# analog_channel.net
KiCad netlist of a schematic drawn in Altium Designer
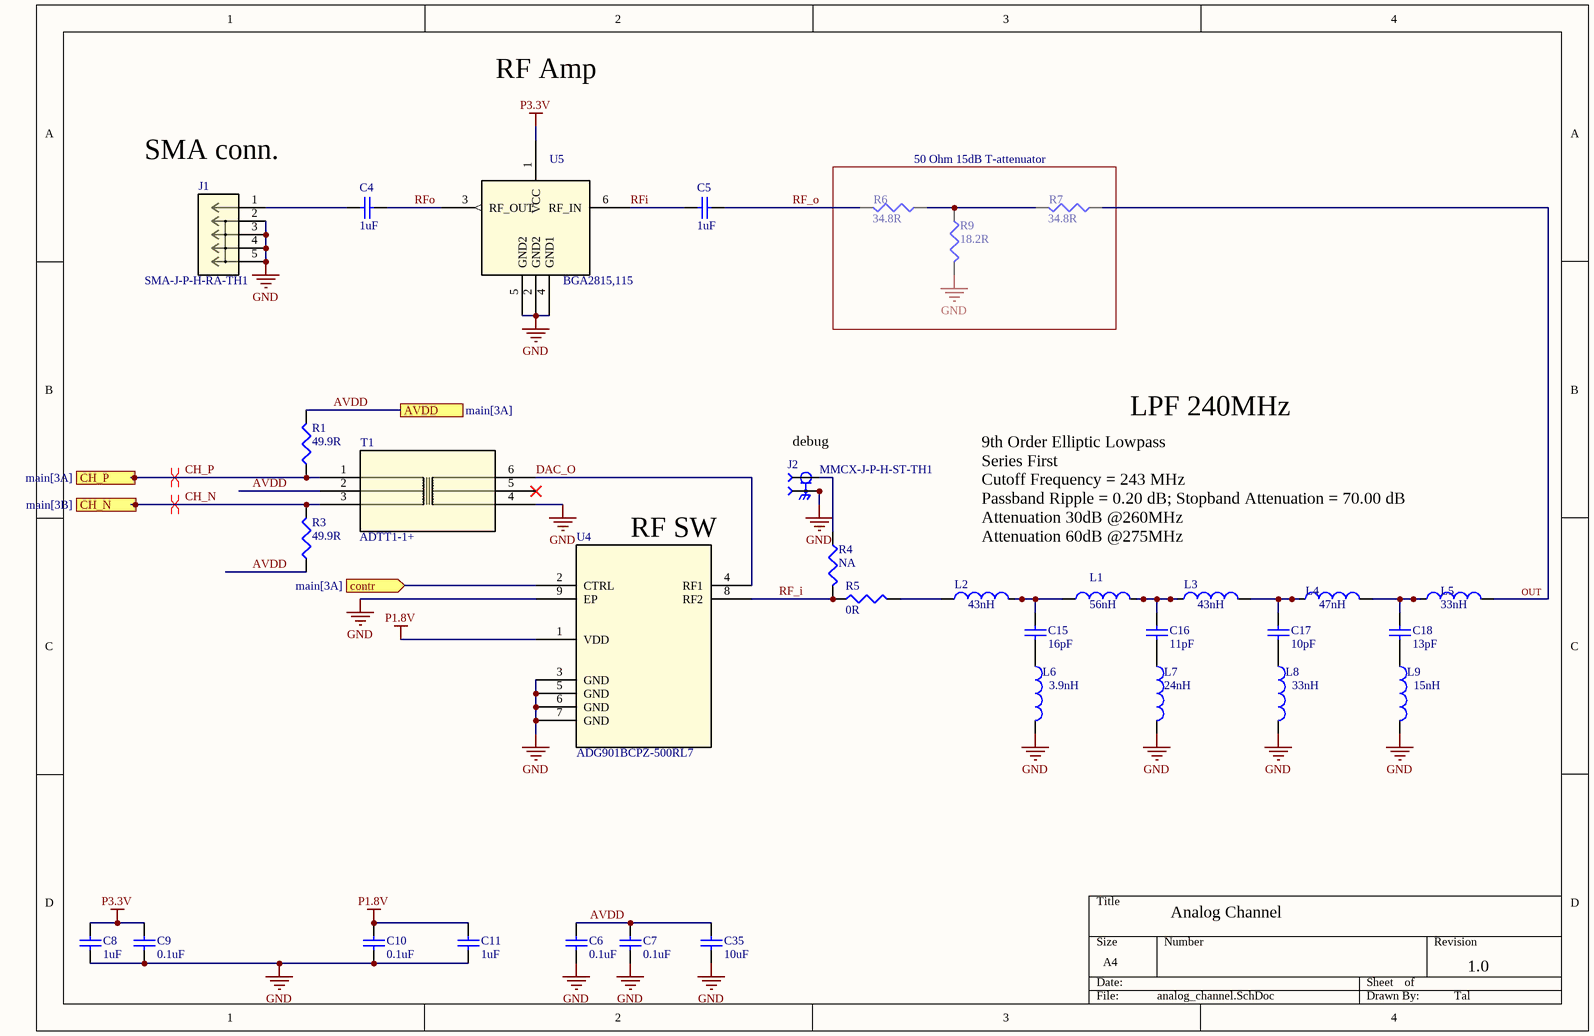
[diagram p0: analog_channel.SchDoc]

(export (version "E")
  (design (tool "Eeschema 10.0.6"))
  (components
    (comp (ref "C4")
      (value "1uF 25V")
      (footprint "Landa_PCB:C0402")
      (description "CAP CER 1uF 25V X5R 0402")
      (fields
        (field (name "MANUFACTURER PART NUMBER") "C1005C0G1H6R8D")
        (field (name "MANUFACTURER") "TDK Corporation")
        (field (name "CAPACITANCE") "1uF")
      )
      (libsource (lib "L_SCH_C") (part "CAP CER 6.8pF 50V NP0 0402"))
    )
    (comp (ref "C5")
      (value "1uF 25V")
      (footprint "Landa_PCB:C0402")
      (description "CAP CER 1uF 25V X5R 0402")
      (fields
        (field (name "MANUFACTURER PART NUMBER") "C1005C0G1H6R8D")
        (field (name "MANUFACTURER") "TDK Corporation")
        (field (name "CAPACITANCE") "1uF")
      )
      (libsource (lib "L_SCH_C") (part "CAP CER 6.8pF 50V NP0 0402"))
    )
    (comp (ref "C6")
      (value "0.1uF 50V")
      (footprint "Landa_PCB:C0402")
      (description "CAP CER 0.1uF 50V NP0 0402")
      (fields
        (field (name "MANUFACTURER PART NUMBER") "C1005C0G1H6R8D")
        (field (name "MANUFACTURER") "TDK Corporation")
        (field (name "CAPACITANCE") "0.1uF")
      )
      (libsource (lib "L_SCH_C") (part "CAP CER 6.8pF 50V NP0 0402"))
    )
    (comp (ref "C7")
      (value "0.1uF 50V")
      (footprint "Landa_PCB:C0402")
      (description "CAP CER 0.1uF 50V NP0 0402")
      (fields
        (field (name "MANUFACTURER PART NUMBER") "C1005C0G1H6R8D")
        (field (name "MANUFACTURER") "TDK Corporation")
        (field (name "CAPACITANCE") "0.1uF")
      )
      (libsource (lib "L_SCH_C") (part "CAP CER 6.8pF 50V NP0 0402"))
    )
    (comp (ref "C8")
      (value "1uF 25V")
      (footprint "Landa_PCB:C0402")
      (description "CAP CER 1uF 25V X5R 0402")
      (fields
        (field (name "MANUFACTURER PART NUMBER") "C1005C0G1H6R8D")
        (field (name "MANUFACTURER") "TDK Corporation")
        (field (name "CAPACITANCE") "1uF")
      )
      (libsource (lib "L_SCH_C") (part "CAP CER 6.8pF 50V NP0 0402"))
    )
    (comp (ref "C9")
      (value "0.1uF 50V")
      (footprint "Landa_PCB:C0402")
      (description "CAP CER 0.1uF 50V NP0 0402")
      (fields
        (field (name "MANUFACTURER PART NUMBER") "C1005C0G1H6R8D")
        (field (name "MANUFACTURER") "TDK Corporation")
        (field (name "CAPACITANCE") "0.1uF")
      )
      (libsource (lib "L_SCH_C") (part "CAP CER 6.8pF 50V NP0 0402"))
    )
    (comp (ref "C10")
      (value "0.1uF 50V")
      (footprint "Landa_PCB:C0402")
      (description "CAP CER 0.1uF 50V NP0 0402")
      (fields
        (field (name "MANUFACTURER PART NUMBER") "C1005C0G1H6R8D")
        (field (name "MANUFACTURER") "TDK Corporation")
        (field (name "CAPACITANCE") "0.1uF")
      )
      (libsource (lib "L_SCH_C") (part "CAP CER 6.8pF 50V NP0 0402"))
    )
    (comp (ref "C11")
      (value "1uF 25V")
      (footprint "Landa_PCB:C0402")
      (description "CAP CER 1uF 25V X5R 0402")
      (fields
        (field (name "MANUFACTURER PART NUMBER") "C1005C0G1H6R8D")
        (field (name "MANUFACTURER") "TDK Corporation")
        (field (name "CAPACITANCE") "1uF")
      )
      (libsource (lib "L_SCH_C") (part "CAP CER 6.8pF 50V NP0 0402"))
    )
    (comp (ref "C15")
      (value "16pF 50V")
      (footprint "Landa_PCB:C0402")
      (description "CAP CER 16PF 50V 5% NP0 0402")
      (fields
        (field (name "MANUFACTURER") "TDK Corporation")
        (field (name "MANUFACTURER PART NUMBER") "C1005C0G1H200J")
        (field (name "CAPACITANCE") "16pF")
      )
      (libsource (lib "L_SCH_C") (part "CAP CER 20pF 50V 5% NP0 0402"))
    )
    (comp (ref "C16")
      (value "11pF 50V")
      (footprint "Landa_PCB:C0402")
      (description "CAP CER 11PF 50V 5% NP0 0402")
      (fields
        (field (name "MANUFACTURER") "TDK Corporation")
        (field (name "MANUFACTURER PART NUMBER") "C1005C0G1H200J")
        (field (name "CAPACITANCE") "11pF")
      )
      (libsource (lib "L_SCH_C") (part "CAP CER 20pF 50V 5% NP0 0402"))
    )
    (comp (ref "C17")
      (value "10pF 50V")
      (footprint "Landa_PCB:C0402")
      (description "CAP CER 10PF 50V 5% NP0 0402")
      (fields
        (field (name "MANUFACTURER") "TDK Corporation")
        (field (name "MANUFACTURER PART NUMBER") "C1005C0G1H200J")
        (field (name "CAPACITANCE") "10pF")
      )
      (libsource (lib "L_SCH_C") (part "CAP CER 20pF 50V 5% NP0 0402"))
    )
    (comp (ref "C18")
      (value "13pF 50V")
      (footprint "Landa_PCB:C0402")
      (description "CAP CER 13PF 50V 5% NP0 0402")
      (fields
        (field (name "MANUFACTURER") "TDK Corporation")
        (field (name "MANUFACTURER PART NUMBER") "C1005C0G1H200J")
        (field (name "CAPACITANCE") "13pF")
      )
      (libsource (lib "L_SCH_C") (part "CAP CER 20pF 50V 5% NP0 0402"))
    )
    (comp (ref "C35")
      (value "10uF 10V")
      (footprint "Landa_PCB:C0402")
      (description "CAP CER 10uF 10V X5R 0402")
      (fields
        (field (name "MANUFACTURER PART NUMBER") "C1005C0G1H6R8D")
        (field (name "MANUFACTURER") "TDK Corporation")
        (field (name "CAPACITANCE") "10uF")
      )
      (libsource (lib "L_SCH_C") (part "CAP CER 6.8pF 50V NP0 0402"))
    )
    (comp (ref "J1")
      (value "SMA-J-P-H-RA-TH1")
      (footprint "CONN_SMA-J-P-H-RA-TH1_SAI")
      (description "No Description Available")
      (fields (field (name "COPYRIGHT") "Copyright (C) 2023 Ultra Librarian. All rights reserved."))
      (libsource (lib "SMA-J-P-H-RA-TH1") (part "SMA-J-P-H-RA-TH1"))
    )
    (comp (ref "J2")
      (value "MMCX-J-P-H-ST-TH1")
      (footprint "SAMTEC_MMCX-J-P-H-ST-TH1")
      (description "MMCX STRAIGHT, THROUGH HOLE JACK- 50 OHM")
      (fields (field (name "MF") "Samtec"))
      (libsource (lib "MMCX-J-P-H-ST-TH1") (part "MMCX-J-P-H-ST-TH1"))
    )
    (comp (ref "L1")
      (value "56nH")
      (footprint "0402-A")
      (description "Inductor")
      (fields (field (name "PUBLISHER") "Altium Limited"))
      (libsource (lib "Miscellaneous Devices") (part "Inductor"))
    )
    (comp (ref "L2")
      (value "43nH")
      (footprint "0402-A")
      (description "Inductor")
      (fields (field (name "PUBLISHER") "Altium Limited"))
      (libsource (lib "Miscellaneous Devices") (part "Inductor"))
    )
    (comp (ref "L3")
      (value "43nH")
      (footprint "0402-A")
      (description "Inductor")
      (fields (field (name "PUBLISHER") "Altium Limited"))
      (libsource (lib "Miscellaneous Devices") (part "Inductor"))
    )
    (comp (ref "L4")
      (value "47nH")
      (footprint "0402-A")
      (description "Inductor")
      (fields (field (name "PUBLISHER") "Altium Limited"))
      (libsource (lib "Miscellaneous Devices") (part "Inductor"))
    )
    (comp (ref "L5")
      (value "33nH")
      (footprint "0402-A")
      (description "Inductor")
      (fields (field (name "PUBLISHER") "Altium Limited"))
      (libsource (lib "Miscellaneous Devices") (part "Inductor"))
    )
    (comp (ref "L6")
      (value "3.9nH")
      (footprint "0402-A")
      (description "Inductor")
      (fields (field (name "PUBLISHER") "Altium Limited"))
      (libsource (lib "Miscellaneous Devices") (part "Inductor"))
    )
    (comp (ref "L7")
      (value "24nH")
      (footprint "0402-A")
      (description "Inductor")
      (fields (field (name "PUBLISHER") "Altium Limited"))
      (libsource (lib "Miscellaneous Devices") (part "Inductor"))
    )
    (comp (ref "L8")
      (value "33nH")
      (footprint "0402-A")
      (description "Inductor")
      (fields (field (name "PUBLISHER") "Altium Limited"))
      (libsource (lib "Miscellaneous Devices") (part "Inductor"))
    )
    (comp (ref "L9")
      (value "15nH")
      (footprint "0402-A")
      (description "Inductor")
      (fields (field (name "PUBLISHER") "Altium Limited"))
      (libsource (lib "Miscellaneous Devices") (part "Inductor"))
    )
    (comp (ref "R1")
      (value "49.9R")
      (footprint "Landa_PCB:R0402")
      (description "RES 49.9 OHM 1/10W 1% 0402 SMD")
      (fields
        (field (name "MANUFACTURER PART NUMBER") "ERJ-2RKF1000X")
        (field (name "MANUFACTURER") "Panasonic Electronic Components")
      )
      (libsource (lib "L_SCH_R") (part "RES 100 OHM 1/10W 1% 0402 SMD"))
    )
    (comp (ref "R3")
      (value "49.9R")
      (footprint "Landa_PCB:R0402")
      (description "RES 49.9 OHM 1/10W 1% 0402 SMD")
      (fields
        (field (name "MANUFACTURER PART NUMBER") "ERJ-2RKF1000X")
        (field (name "MANUFACTURER") "Panasonic Electronic Components")
      )
      (libsource (lib "L_SCH_R") (part "RES 100 OHM 1/10W 1% 0402 SMD"))
    )
    (comp (ref "R4")
      (value "NA")
      (footprint "r0402")
      (description "RES 0 OHM 1/10W 1% 0402 SMD")
      (fields
        (field (name "MANUFACTURER PART NUMBER") "ERJ-2RKF1000X")
        (field (name "MANUFACTURER") "Panasonic Electronic Components")
      )
      (libsource (lib "L_SCH_R") (part "RES 100 OHM 1/10W 1% 0402 SMD"))
    )
    (comp (ref "R5")
      (value "0R")
      (footprint "r0402")
      (description "RES 0 OHM 1/10W 1% 0402 SMD")
      (fields
        (field (name "MANUFACTURER PART NUMBER") "ERJ-2RKF1000X")
        (field (name "MANUFACTURER") "Panasonic Electronic Components")
      )
      (libsource (lib "L_SCH_R") (part "RES 100 OHM 1/10W 1% 0402 SMD"))
    )
    (comp (ref "R6")
      (value "34.8R")
      (footprint "r0402")
      (description "RES 34.8 OHM 1/10W 1% 0402 SMD")
      (fields
        (field (name "MANUFACTURER PART NUMBER") "ERJ-2RKF1000X")
        (field (name "MANUFACTURER") "Panasonic Electronic Components")
      )
      (libsource (lib "L_SCH_R") (part "RES 100 OHM 1/10W 1% 0402 SMD"))
    )
    (comp (ref "R7")
      (value "34.8R")
      (footprint "r0402")
      (description "RES 34.8 OHM 1/10W 1% 0402 SMD")
      (fields
        (field (name "MANUFACTURER PART NUMBER") "ERJ-2RKF1000X")
        (field (name "MANUFACTURER") "Panasonic Electronic Components")
      )
      (libsource (lib "L_SCH_R") (part "RES 100 OHM 1/10W 1% 0402 SMD"))
    )
    (comp (ref "R9")
      (value "18.2R")
      (footprint "r0402")
      (description "RES 18.2 OHM 1/10W 1% 0402 SMD")
      (fields
        (field (name "MANUFACTURER PART NUMBER") "ERJ-2RKF1000X")
        (field (name "MANUFACTURER") "Panasonic Electronic Components")
      )
      (libsource (lib "L_SCH_R") (part "RES 100 OHM 1/10W 1% 0402 SMD"))
    )
    (comp (ref "T1")
      (value "ADTT1-1+")
      (footprint "CD542_MNC")
      (description "No Description Available")
      (fields (field (name "COPYRIGHT") "Copyright (C) 2023 Ultra Librarian. All rights reserved."))
      (libsource (lib "ADTT1-1&plus_") (part "ADTT1-1+"))
    )
    (comp (ref "U4")
      (value "ADG901BCPZ-500RL7")
      (footprint "CP_8_2_ADI")
      (description "No Description Available")
      (fields (field (name "COPYRIGHT") "Copyright (C) 2023 Ultra Librarian. All rights reserved."))
      (libsource (lib "ADG901BCPZ-500RL7") (part "ADG901BCPZ-500RL7"))
    )
    (comp (ref "U5")
      (value "BGA2815,115")
      (footprint "SOT_2815,115_NXP")
      (description "No Description Available")
      (fields (field (name "COPYRIGHT") "Copyright (C) 2023 Ultra Librarian. All rights reserved."))
      (libsource (lib "BGA2815,115") (part "BGA2815,115"))
    )
  )
  (nets
    (net (code "1") (name "/AVDD") (class "Default")
      (node (ref "C35") (pin "2") (pinfunction "2_2") (pintype "passive"))
      (node (ref "C6") (pin "2") (pinfunction "2_2") (pintype "passive"))
      (node (ref "C7") (pin "2") (pinfunction "2_2") (pintype "passive"))
      (node (ref "R1") (pin "2") (pinfunction "2_2") (pintype "passive"))
      (node (ref "R3") (pin "1") (pinfunction "1_1") (pintype "passive"))
      (node (ref "T1") (pin "2") (pinfunction "2_2") (pintype "passive"))
    )
    (net (code "2") (name "/CH_N") (class "Default")
      (node (ref "R3") (pin "2") (pinfunction "2_2") (pintype "passive"))
      (node (ref "T1") (pin "3") (pinfunction "3_3") (pintype "passive"))
    )
    (net (code "3") (name "/CH_P") (class "Default")
      (node (ref "R1") (pin "1") (pinfunction "1_1") (pintype "passive"))
      (node (ref "T1") (pin "1") (pinfunction "1_1") (pintype "passive"))
    )
    (net (code "4") (name "/DAC_O") (class "Default")
      (node (ref "T1") (pin "6") (pinfunction "6_6") (pintype "passive"))
      (node (ref "U4") (pin "4") (pinfunction "RF1_4") (pintype "passive"))
    )
    (net (code "5") (name "/OUT") (class "Default")
      (node (ref "L5") (pin "2") (pinfunction "2_2") (pintype "passive"))
      (node (ref "R7") (pin "1") (pinfunction "1_1") (pintype "passive"))
    )
    (net (code "6") (name "/RF_i") (class "Default")
      (node (ref "R4") (pin "2") (pinfunction "2_2") (pintype "passive"))
      (node (ref "R5") (pin "1") (pinfunction "1_1") (pintype "passive"))
      (node (ref "U4") (pin "8") (pinfunction "RF2_8") (pintype "passive"))
    )
    (net (code "7") (name "/RF_o") (class "Default")
      (node (ref "C5") (pin "2") (pinfunction "2_2") (pintype "passive"))
      (node (ref "R6") (pin "2") (pinfunction "2_2") (pintype "passive"))
    )
    (net (code "8") (name "/RFi") (class "Default")
      (node (ref "C5") (pin "1") (pinfunction "1_1") (pintype "passive"))
      (node (ref "U5") (pin "6") (pinfunction "RF_IN_6") (pintype "passive"))
    )
    (net (code "9") (name "/RFo") (class "Default")
      (node (ref "C4") (pin "2") (pinfunction "2_2") (pintype "passive"))
      (node (ref "U5") (pin "3") (pinfunction "RF_OUT_3") (pintype "output"))
    )
    (net (code "10") (name "/contr") (class "Default")
      (node (ref "U4") (pin "2") (pinfunction "CTRL_2") (pintype "passive"))
    )
    (net (code "11") (name "GND") (class "Default")
      (node (ref "C10") (pin "1") (pinfunction "1_1") (pintype "passive"))
      (node (ref "C11") (pin "1") (pinfunction "1_1") (pintype "passive"))
      (node (ref "C35") (pin "1") (pinfunction "1_1") (pintype "passive"))
      (node (ref "C6") (pin "1") (pinfunction "1_1") (pintype "passive"))
      (node (ref "C7") (pin "1") (pinfunction "1_1") (pintype "passive"))
      (node (ref "C8") (pin "1") (pinfunction "1_1") (pintype "passive"))
      (node (ref "C9") (pin "1") (pinfunction "1_1") (pintype "passive"))
      (node (ref "J1") (pin "2") (pinfunction "2_2") (pintype "passive"))
      (node (ref "J1") (pin "3") (pinfunction "3_3") (pintype "passive"))
      (node (ref "J1") (pin "4") (pinfunction "4_4") (pintype "passive"))
      (node (ref "J1") (pin "5") (pinfunction "5_5") (pintype "passive"))
      (node (ref "J2") (pin "S1") (pinfunction "2_S1") (pintype "passive"))
      (node (ref "J2") (pin "S2") (pinfunction "2_S2") (pintype "passive"))
      (node (ref "J2") (pin "S3") (pinfunction "2_S3") (pintype "passive"))
      (node (ref "J2") (pin "S4") (pinfunction "2_S4") (pintype "passive"))
      (node (ref "L6") (pin "2") (pinfunction "2_2") (pintype "passive"))
      (node (ref "L7") (pin "2") (pinfunction "2_2") (pintype "passive"))
      (node (ref "L8") (pin "2") (pinfunction "2_2") (pintype "passive"))
      (node (ref "L9") (pin "2") (pinfunction "2_2") (pintype "passive"))
      (node (ref "R9") (pin "2") (pinfunction "2_2") (pintype "passive"))
      (node (ref "T1") (pin "4") (pinfunction "4_4") (pintype "passive"))
      (node (ref "U4") (pin "3") (pinfunction "GND_3") (pintype "passive"))
      (node (ref "U4") (pin "5") (pinfunction "GND_5") (pintype "passive"))
      (node (ref "U4") (pin "6") (pinfunction "GND_6") (pintype "passive"))
      (node (ref "U4") (pin "7") (pinfunction "GND_7") (pintype "passive"))
      (node (ref "U4") (pin "9") (pinfunction "EP_9") (pintype "passive"))
      (node (ref "U5") (pin "2") (pinfunction "GND2_2") (pintype "passive"))
      (node (ref "U5") (pin "4") (pinfunction "GND1_4") (pintype "passive"))
      (node (ref "U5") (pin "5") (pinfunction "GND2_5") (pintype "passive"))
    )
    (net (code "12") (name "Net-(C4-Pad1)") (class "Default")
      (node (ref "C4") (pin "1") (pinfunction "1_1") (pintype "passive"))
      (node (ref "J1") (pin "1") (pinfunction "1_1") (pintype "passive"))
    )
    (net (code "13") (name "Net-(C15-Pad1)") (class "Default")
      (node (ref "C15") (pin "1") (pinfunction "1_1") (pintype "passive"))
      (node (ref "L1") (pin "1") (pinfunction "1_1") (pintype "passive"))
      (node (ref "L2") (pin "2") (pinfunction "2_2") (pintype "passive"))
    )
    (net (code "14") (name "Net-(C15-Pad2)") (class "Default")
      (node (ref "C15") (pin "2") (pinfunction "2_2") (pintype "passive"))
      (node (ref "L6") (pin "1") (pinfunction "1_1") (pintype "passive"))
    )
    (net (code "15") (name "Net-(C16-Pad1)") (class "Default")
      (node (ref "C16") (pin "1") (pinfunction "1_1") (pintype "passive"))
      (node (ref "L1") (pin "2") (pinfunction "2_2") (pintype "passive"))
      (node (ref "L3") (pin "1") (pinfunction "1_1") (pintype "passive"))
    )
    (net (code "16") (name "Net-(C16-Pad2)") (class "Default")
      (node (ref "C16") (pin "2") (pinfunction "2_2") (pintype "passive"))
      (node (ref "L7") (pin "1") (pinfunction "1_1") (pintype "passive"))
    )
    (net (code "17") (name "Net-(C17-Pad1)") (class "Default")
      (node (ref "C17") (pin "1") (pinfunction "1_1") (pintype "passive"))
      (node (ref "L3") (pin "2") (pinfunction "2_2") (pintype "passive"))
      (node (ref "L4") (pin "1") (pinfunction "1_1") (pintype "passive"))
    )
    (net (code "18") (name "Net-(C17-Pad2)") (class "Default")
      (node (ref "C17") (pin "2") (pinfunction "2_2") (pintype "passive"))
      (node (ref "L8") (pin "1") (pinfunction "1_1") (pintype "passive"))
    )
    (net (code "19") (name "Net-(C18-Pad1)") (class "Default")
      (node (ref "C18") (pin "1") (pinfunction "1_1") (pintype "passive"))
      (node (ref "L4") (pin "2") (pinfunction "2_2") (pintype "passive"))
      (node (ref "L5") (pin "1") (pinfunction "1_1") (pintype "passive"))
    )
    (net (code "20") (name "Net-(C18-Pad2)") (class "Default")
      (node (ref "C18") (pin "2") (pinfunction "2_2") (pintype "passive"))
      (node (ref "L9") (pin "1") (pinfunction "1_1") (pintype "passive"))
    )
    (net (code "21") (name "Net-(J2-Pad1)") (class "Default")
      (node (ref "J2") (pin "1") (pinfunction "1_1") (pintype "passive"))
      (node (ref "R4") (pin "1") (pinfunction "1_1") (pintype "passive"))
    )
    (net (code "22") (name "Net-(L2-Pad1)") (class "Default")
      (node (ref "L2") (pin "1") (pinfunction "1_1") (pintype "passive"))
      (node (ref "R5") (pin "2") (pinfunction "2_2") (pintype "passive"))
    )
    (net (code "23") (name "Net-(R6-Pad1)") (class "Default")
      (node (ref "R6") (pin "1") (pinfunction "1_1") (pintype "passive"))
      (node (ref "R7") (pin "2") (pinfunction "2_2") (pintype "passive"))
      (node (ref "R9") (pin "1") (pinfunction "1_1") (pintype "passive"))
    )
    (net (code "24") (name "P1.8V") (class "Default")
      (node (ref "C10") (pin "2") (pinfunction "2_2") (pintype "passive"))
      (node (ref "C11") (pin "2") (pinfunction "2_2") (pintype "passive"))
      (node (ref "U4") (pin "1") (pinfunction "VDD_1") (pintype "power_in"))
    )
    (net (code "25") (name "P3.3V") (class "Default")
      (node (ref "C8") (pin "2") (pinfunction "2_2") (pintype "passive"))
      (node (ref "C9") (pin "2") (pinfunction "2_2") (pintype "passive"))
      (node (ref "U5") (pin "1") (pinfunction "VCC_1") (pintype "power_in"))
    )
    (net (code "26") (name "unconnected-(T1-Pad5)") (class "Default")
      (node (ref "T1") (pin "5") (pinfunction "5_5") (pintype "passive+no_connect"))
    )
  )
)
